# integrated_driver_and_current_sense.net
KiCad netlist of a schematic drawn in Altium Designer
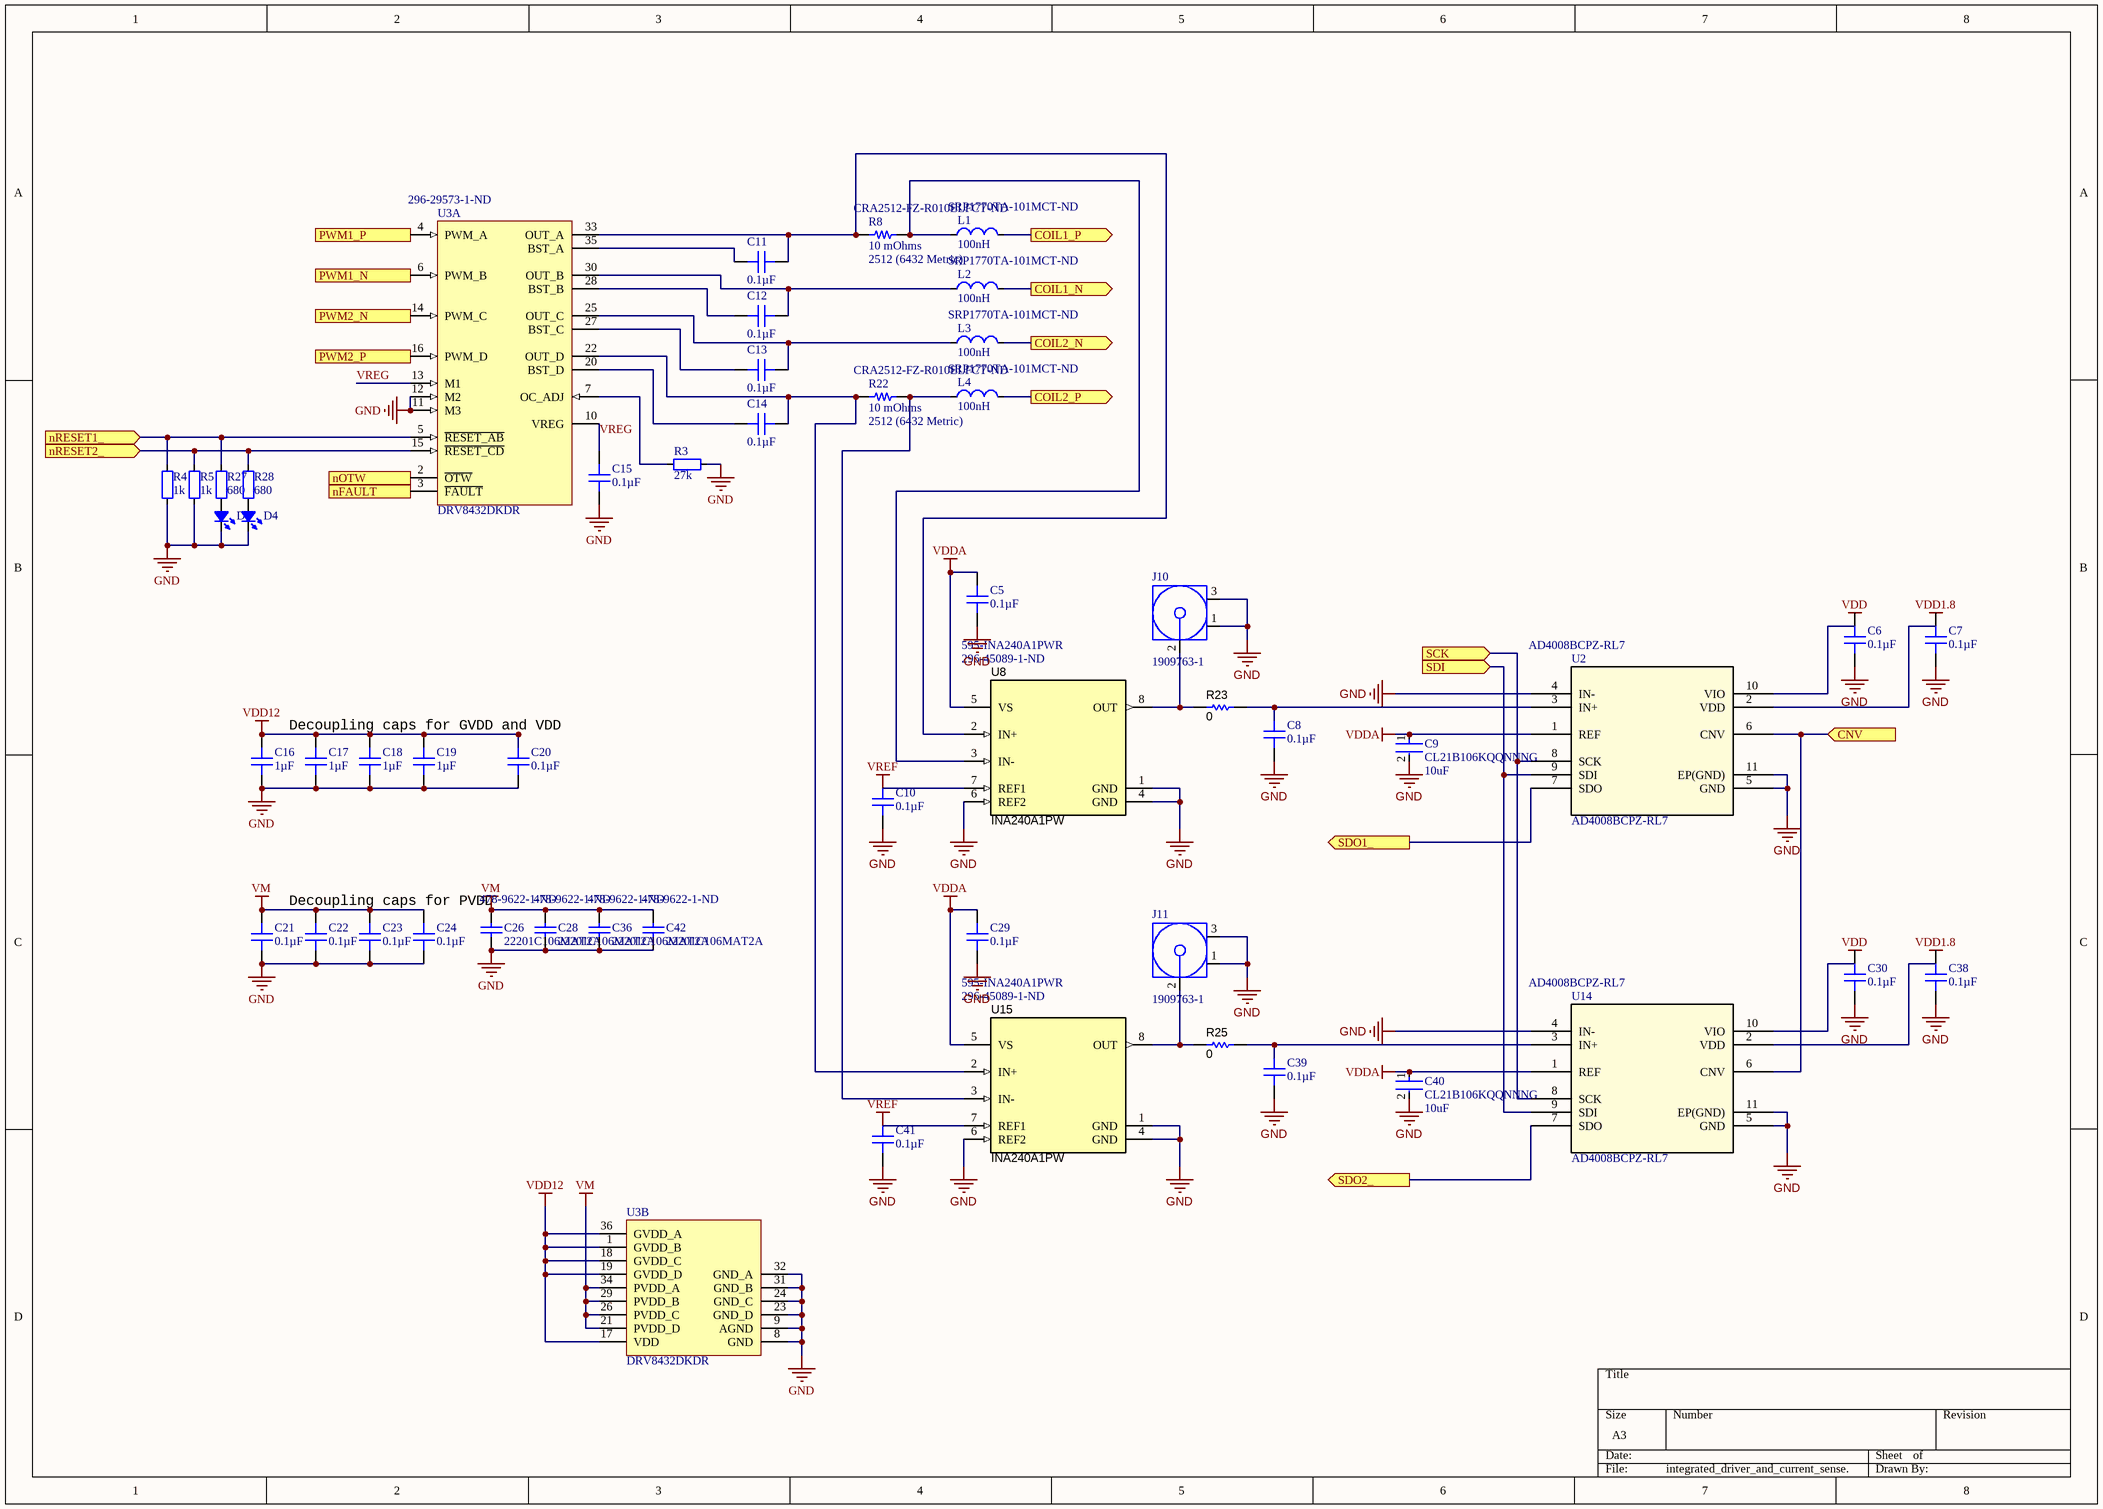
[diagram p0: integrated_driver_and_current_sense.SchDoc]

(export (version "E")
  (design (tool "Eeschema 10.0.6"))
  (components
    (comp (ref "C5")
      (value "0.1µF")
      (footprint "CAP 0402_1005")
      (description "CAP CER 0.1UF 25V X7R 0402")
      (fields (field (name "MANUFACTURER") "AVX Corporation") (field (name "PART NUMBER") "04023C104KAT2A"))
      (libsource (lib "Celestial Altium Library - altium_library") (part "Capacitor"))
    )
    (comp (ref "C6")
      (value "0.1µF")
      (footprint "CAP 0402_1005")
      (description "CAP CER 0.1UF 25V X7R 0402")
      (fields (field (name "MANUFACTURER") "AVX Corporation") (field (name "PART NUMBER") "04023C104KAT2A"))
      (libsource (lib "Celestial Altium Library - altium_library") (part "Capacitor"))
    )
    (comp (ref "C7")
      (value "0.1µF")
      (footprint "CAP 0402_1005")
      (description "CAP CER 0.1UF 25V X7R 0402")
      (fields (field (name "MANUFACTURER") "AVX Corporation") (field (name "PART NUMBER") "04023C104KAT2A"))
      (libsource (lib "Celestial Altium Library - altium_library") (part "Capacitor"))
    )
    (comp (ref "C8")
      (value "0.1µF")
      (footprint "CAP 0402_1005")
      (description "CAP CER 0.1UF 25V X7R 0402")
      (fields (field (name "MANUFACTURER") "AVX Corporation") (field (name "PART NUMBER") "04023C104KAT2A"))
      (libsource (lib "Celestial Altium Library - altium_library") (part "Capacitor"))
    )
    (comp (ref "C9")
      (value "CL21B106KQQNNNG")
      (footprint "FP-CL21-IPC_C")
      (description "CL21 Series 0805 10uF 6.3V ±10% Tolerance X7R Multilayer Ceramic Chip Capacitor")
      (fields
        (field (name "CAPACITANCE") "10uF")
        (field (name "TOLERANCE") "10%")
        (field (name "VOLTAGE") "6.3V")
      )
      (libsource (lib "Altium Content Vault") (part "b4654b650e69147ec39a6b967a45e02"))
    )
    (comp (ref "C10")
      (value "0.1µF")
      (footprint "CAP 0402_1005")
      (description "CAP CER 0.1UF 25V X7R 0402")
      (fields (field (name "MANUFACTURER") "AVX Corporation") (field (name "PART NUMBER") "04023C104KAT2A"))
      (libsource (lib "Celestial Altium Library - altium_library") (part "Capacitor"))
    )
    (comp (ref "C11")
      (value "0.1µF")
      (footprint "CAP 0603_1608")
      (description "CAP CER 0.1UF 100V X7R 0603")
      (fields (field (name "PART NUMBER") "06031C104KAT2A") (field (name "MANUFACTURER") "AVX Corporation"))
      (libsource (lib "Celestial Altium Library - altium_library") (part "Capacitor"))
    )
    (comp (ref "C12")
      (value "0.1µF")
      (footprint "CAP 0603_1608")
      (description "CAP CER 0.1UF 100V X7R 0603")
      (fields (field (name "PART NUMBER") "06031C104KAT2A") (field (name "MANUFACTURER") "AVX Corporation"))
      (libsource (lib "Celestial Altium Library - altium_library") (part "Capacitor"))
    )
    (comp (ref "C13")
      (value "0.1µF")
      (footprint "CAP 0603_1608")
      (description "CAP CER 0.1UF 100V X7R 0603")
      (fields (field (name "PART NUMBER") "06031C104KAT2A") (field (name "MANUFACTURER") "AVX Corporation"))
      (libsource (lib "Celestial Altium Library - altium_library") (part "Capacitor"))
    )
    (comp (ref "C14")
      (value "0.1µF")
      (footprint "CAP 0603_1608")
      (description "CAP CER 0.1UF 100V X7R 0603")
      (fields (field (name "PART NUMBER") "06031C104KAT2A") (field (name "MANUFACTURER") "AVX Corporation"))
      (libsource (lib "Celestial Altium Library - altium_library") (part "Capacitor"))
    )
    (comp (ref "C15")
      (value "0.1µF")
      (footprint "CAP 0402_1005")
      (description "CAP CER 0.1UF 25V X7R 0402")
      (fields (field (name "PART NUMBER") "04023C104KAT2A") (field (name "MANUFACTURER") "AVX Corporation"))
      (libsource (lib "Celestial Altium Library - altium_library") (part "Capacitor"))
    )
    (comp (ref "C16")
      (value "1µF")
      (footprint "CAP 0603_1608")
      (description "CAP CER 1UF 25V X7R 0603")
      (fields (field (name "PART NUMBER") "TMK107B7105KA-T") (field (name "MANUFACTURER") "Taiyo Yuden"))
      (libsource (lib "Celestial Altium Library - altium_library") (part "Capacitor"))
    )
    (comp (ref "C17")
      (value "1µF")
      (footprint "CAP 0603_1608")
      (description "CAP CER 1UF 25V X7R 0603")
      (fields (field (name "PART NUMBER") "TMK107B7105KA-T") (field (name "MANUFACTURER") "Taiyo Yuden"))
      (libsource (lib "Celestial Altium Library - altium_library") (part "Capacitor"))
    )
    (comp (ref "C18")
      (value "1µF")
      (footprint "CAP 0603_1608")
      (description "CAP CER 1UF 25V X7R 0603")
      (fields (field (name "PART NUMBER") "TMK107B7105KA-T") (field (name "MANUFACTURER") "Taiyo Yuden"))
      (libsource (lib "Celestial Altium Library - altium_library") (part "Capacitor"))
    )
    (comp (ref "C19")
      (value "1µF")
      (footprint "CAP 0603_1608")
      (description "CAP CER 1UF 25V X7R 0603")
      (fields (field (name "PART NUMBER") "TMK107B7105KA-T") (field (name "MANUFACTURER") "Taiyo Yuden"))
      (libsource (lib "Celestial Altium Library - altium_library") (part "Capacitor"))
    )
    (comp (ref "C20")
      (value "0.1µF")
      (footprint "CAP 0402_1005")
      (description "CAP CER 0.1UF 25V X7R 0402")
      (fields (field (name "MANUFACTURER") "AVX Corporation") (field (name "PART NUMBER") "04023C104KAT2A"))
      (libsource (lib "Celestial Altium Library - altium_library") (part "Capacitor"))
    )
    (comp (ref "C21")
      (value "0.1µF")
      (footprint "CAP 0603_1608")
      (description "CAP CER 0.1UF 100V X7R 0603")
      (fields (field (name "PART NUMBER") "06031C104KAT2A") (field (name "MANUFACTURER") "AVX Corporation"))
      (libsource (lib "Celestial Altium Library - altium_library") (part "Capacitor"))
    )
    (comp (ref "C22")
      (value "0.1µF")
      (footprint "CAP 0603_1608")
      (description "CAP CER 0.1UF 100V X7R 0603")
      (fields (field (name "PART NUMBER") "06031C104KAT2A") (field (name "MANUFACTURER") "AVX Corporation"))
      (libsource (lib "Celestial Altium Library - altium_library") (part "Capacitor"))
    )
    (comp (ref "C23")
      (value "0.1µF")
      (footprint "CAP 0603_1608")
      (description "CAP CER 0.1UF 100V X7R 0603")
      (fields (field (name "PART NUMBER") "06031C104KAT2A") (field (name "MANUFACTURER") "AVX Corporation"))
      (libsource (lib "Celestial Altium Library - altium_library") (part "Capacitor"))
    )
    (comp (ref "C24")
      (value "0.1µF")
      (footprint "CAP 0603_1608")
      (description "CAP CER 0.1UF 100V X7R 0603")
      (fields (field (name "PART NUMBER") "06031C104KAT2A") (field (name "MANUFACTURER") "AVX Corporation"))
      (libsource (lib "Celestial Altium Library - altium_library") (part "Capacitor"))
    )
    (comp (ref "C26")
      (value "22201C106MAT2A")
      (footprint "CAPC5750X279X64NL40T39")
      (description "Cap Ceramic 10uF 100V X7R 20% SMD 2220 125°C Embossed T/R")
      (fields (field (name "MANUFACTURER") "AVX") (field (name "SUPPLIER PART NUMBER 1") "478-9622-1-ND"))
      (libsource (lib "Altium Content Vault") (part "CAP-NP-2"))
    )
    (comp (ref "C28")
      (value "22201C106MAT2A")
      (footprint "CAPC5750X279X64NL40T39")
      (description "Cap Ceramic 10uF 100V X7R 20% SMD 2220 125°C Embossed T/R")
      (fields (field (name "MANUFACTURER") "AVX") (field (name "SUPPLIER PART NUMBER 1") "478-9622-1-ND"))
      (libsource (lib "Altium Content Vault") (part "CAP-NP-2"))
    )
    (comp (ref "C29")
      (value "0.1µF")
      (footprint "CAP 0402_1005")
      (description "CAP CER 0.1UF 25V X7R 0402")
      (fields (field (name "MANUFACTURER") "AVX Corporation") (field (name "PART NUMBER") "04023C104KAT2A"))
      (libsource (lib "Celestial Altium Library - altium_library") (part "Capacitor"))
    )
    (comp (ref "C30")
      (value "0.1µF")
      (footprint "CAP 0402_1005")
      (description "CAP CER 0.1UF 25V X7R 0402")
      (fields (field (name "MANUFACTURER") "AVX Corporation") (field (name "PART NUMBER") "04023C104KAT2A"))
      (libsource (lib "Celestial Altium Library - altium_library") (part "Capacitor"))
    )
    (comp (ref "C36")
      (value "22201C106MAT2A")
      (footprint "CAPC5750X279X64NL40T39")
      (description "Cap Ceramic 10uF 100V X7R 20% SMD 2220 125°C Embossed T/R")
      (fields (field (name "MANUFACTURER") "AVX") (field (name "SUPPLIER PART NUMBER 1") "478-9622-1-ND"))
      (libsource (lib "Altium Content Vault") (part "CAP-NP-2"))
    )
    (comp (ref "C38")
      (value "0.1µF")
      (footprint "CAP 0402_1005")
      (description "CAP CER 0.1UF 25V X7R 0402")
      (fields (field (name "MANUFACTURER") "AVX Corporation") (field (name "PART NUMBER") "04023C104KAT2A"))
      (libsource (lib "Celestial Altium Library - altium_library") (part "Capacitor"))
    )
    (comp (ref "C39")
      (value "0.1µF")
      (footprint "CAP 0402_1005")
      (description "CAP CER 0.1UF 25V X7R 0402")
      (fields (field (name "MANUFACTURER") "AVX Corporation") (field (name "PART NUMBER") "04023C104KAT2A"))
      (libsource (lib "Celestial Altium Library - altium_library") (part "Capacitor"))
    )
    (comp (ref "C40")
      (value "CL21B106KQQNNNG")
      (footprint "FP-CL21-IPC_C")
      (description "CL21 Series 0805 10uF 6.3V ±10% Tolerance X7R Multilayer Ceramic Chip Capacitor")
      (fields
        (field (name "CAPACITANCE") "10uF")
        (field (name "TOLERANCE") "10%")
        (field (name "VOLTAGE") "6.3V")
      )
      (libsource (lib "Altium Content Vault") (part "b4654b650e69147ec39a6b967a45e02"))
    )
    (comp (ref "C41")
      (value "0.1µF")
      (footprint "CAP 0402_1005")
      (description "CAP CER 0.1UF 25V X7R 0402")
      (fields (field (name "MANUFACTURER") "AVX Corporation") (field (name "PART NUMBER") "04023C104KAT2A"))
      (libsource (lib "Celestial Altium Library - altium_library") (part "Capacitor"))
    )
    (comp (ref "C42")
      (value "22201C106MAT2A")
      (footprint "CAPC5750X279X64NL40T39")
      (description "Cap Ceramic 10uF 100V X7R 20% SMD 2220 125°C Embossed T/R")
      (fields (field (name "MANUFACTURER") "AVX") (field (name "SUPPLIER PART NUMBER 1") "478-9622-1-ND"))
      (libsource (lib "Altium Content Vault") (part "CAP-NP-2"))
    )
    (comp (ref "D3")
      (value "LED_0402")
      (footprint "PCB_ActiveLED:LED_0402_RED")
      (description "LED")
      (libsource (lib "SCH_Active") (part "LED_0402"))
    )
    (comp (ref "D4")
      (value "LED_0402")
      (footprint "PCB_ActiveLED:LED_0402_RED")
      (description "LED")
      (libsource (lib "SCH_Active") (part "LED_0402"))
    )
    (comp (ref "J10")
      (value "1909763-1")
      (footprint "TECO-1909763-1_V")
      (description "Ultra Miniature Coaxial Connector Jack, 60 V, 50 Ohm, -40 to 90 degC, RoHS, Tape and Reel")
      (fields (field (name "MANUFACTURER") "TE Connectivity"))
      (libsource (lib "Altium Content Vault") (part "CN-1P-M-RF3"))
    )
    (comp (ref "J11")
      (value "1909763-1")
      (footprint "TECO-1909763-1_V")
      (description "Ultra Miniature Coaxial Connector Jack, 60 V, 50 Ohm, -40 to 90 degC, RoHS, Tape and Reel")
      (fields (field (name "MANUFACTURER") "TE Connectivity"))
      (libsource (lib "Altium Content Vault") (part "CN-1P-M-RF3"))
    )
    (comp (ref "L1")
      (value "100nH")
      (footprint "SRP1770TA")
      (description "FIXED IND 100UH 5.3A 118 MOHM")
      (fields
        (field (name "MANUFACTURER") "TDK")
        (field (name "MANUFACTURER PART NUMBER") "MPZ2012S300AT000")
        (field (name "SUPPLIER PART NUMBER 1") "SRP1770TA-101MCT-ND")
      )
      (libsource (lib "SCH_Passive") (part "Ind_0805"))
    )
    (comp (ref "L2")
      (value "100nH")
      (footprint "SRP1770TA")
      (description "FIXED IND 100UH 5.3A 118 MOHM")
      (fields
        (field (name "MANUFACTURER") "TDK")
        (field (name "MANUFACTURER PART NUMBER") "MPZ2012S300AT000")
        (field (name "SUPPLIER PART NUMBER 1") "SRP1770TA-101MCT-ND")
      )
      (libsource (lib "SCH_Passive") (part "Ind_0805"))
    )
    (comp (ref "L3")
      (value "100nH")
      (footprint "SRP1770TA")
      (description "FIXED IND 100UH 5.3A 118 MOHM")
      (fields
        (field (name "MANUFACTURER") "TDK")
        (field (name "MANUFACTURER PART NUMBER") "MPZ2012S300AT000")
        (field (name "SUPPLIER PART NUMBER 1") "SRP1770TA-101MCT-ND")
      )
      (libsource (lib "SCH_Passive") (part "Ind_0805"))
    )
    (comp (ref "L4")
      (value "100nH")
      (footprint "SRP1770TA")
      (description "FIXED IND 100UH 5.3A 118 MOHM")
      (fields
        (field (name "MANUFACTURER") "TDK")
        (field (name "MANUFACTURER PART NUMBER") "MPZ2012S300AT000")
        (field (name "SUPPLIER PART NUMBER 1") "SRP1770TA-101MCT-ND")
      )
      (libsource (lib "SCH_Passive") (part "Ind_0805"))
    )
    (comp (ref "R3")
      (value "27k")
      (footprint "PCB_PassiveRes:RES_0402")
      (description "Resistor")
      (fields (field (name "Comment") "Res_0402"))
      (libsource (lib "") (part "Res_0402_1"))
    )
    (comp (ref "R4")
      (value "1k")
      (footprint "PCB_PassiveRes:RES_0805")
      (description "Resistor")
      (fields (field (name "Comment") "Res_0805"))
      (libsource (lib "SCH_Passive") (part "Res_0805"))
    )
    (comp (ref "R5")
      (value "1k")
      (footprint "PCB_PassiveRes:RES_0805")
      (description "Resistor")
      (fields (field (name "Comment") "Res_0805"))
      (libsource (lib "SCH_Passive") (part "Res_0805"))
    )
    (comp (ref "R8")
      (value "10 mOhms")
      (footprint "STACKPOLE CSR2512")
      (description "RES 0.01 OHM 1% 2W 2512")
      (fields
        (field (name "PART NUMBER") "TLR3A20ER010FTDG")
        (field (name "PACKAGE / CASE") "2512 (6432 Metric)")
        (field (name "MANUFACTURER") "TE Connectivity Passive Product")
        (field (name "SUPPLIER PART NUMBER 1") "CRA2512-FZ-R010ELFCT-ND")
      )
      (libsource (lib "Celestial Altium Library - altium_library") (part "Resistor"))
    )
    (comp (ref "R22")
      (value "10 mOhms")
      (footprint "STACKPOLE CSR2512")
      (description "RES 0.01 OHM 1% 2W 2512")
      (fields
        (field (name "PART NUMBER") "TLR3A20ER010FTDG")
        (field (name "PACKAGE / CASE") "2512 (6432 Metric)")
        (field (name "MANUFACTURER") "TE Connectivity Passive Product")
        (field (name "SUPPLIER PART NUMBER 1") "CRA2512-FZ-R010ELFCT-ND")
      )
      (libsource (lib "Celestial Altium Library - altium_library") (part "Resistor"))
    )
    (comp (ref "R23")
      (value "CRCW04020000Z0ED")
      (footprint "RES_0402")
      (description "RES, 0, 5%, 0.063 W, 0402")
      (fields
        (field (name "VALUEDISPLAYED") "0")
        (field (name "MANUFACTURER") "Vishay-Dale")
        (field (name "PUBLISHER") "Texas Instruments")
      )
      (libsource (lib "Resistor_0402") (part "CRCW04020000Z0ED"))
    )
    (comp (ref "R25")
      (value "CRCW04020000Z0ED")
      (footprint "RES_0402")
      (description "RES, 0, 5%, 0.063 W, 0402")
      (fields
        (field (name "VALUEDISPLAYED") "0")
        (field (name "MANUFACTURER") "Vishay-Dale")
        (field (name "PUBLISHER") "Texas Instruments")
      )
      (libsource (lib "Resistor_0402") (part "CRCW04020000Z0ED"))
    )
    (comp (ref "R27")
      (value "680")
      (footprint "PCB_PassiveRes:RES_0402")
      (description "Resistor")
      (fields (field (name "Comment") "Res_0402"))
      (libsource (lib "SCH_Passive") (part "Res_0402"))
    )
    (comp (ref "R28")
      (value "680")
      (footprint "PCB_PassiveRes:RES_0402")
      (description "Resistor")
      (fields (field (name "Comment") "Res_0402"))
      (libsource (lib "SCH_Passive") (part "Res_0402"))
    )
    (comp (ref "U2")
      (value "AD4008BCPZ-RL7")
      (footprint "CP_10_9")
      (description "16-Bit, 2 MSPS/1 MSPS/500 kSPS,\r\nPrecision, Pseudo Differential, SAR ADCs")
      (fields (field (name "SUPPLIER PART NUMBER 1") "AD4008BCPZ-RL7"))
      (libsource (lib "2018-05-09_17-49-12") (part "AD4008BCPZ-RL7"))
    )
    (comp (ref "U3")
      (value "DRV8432DKDR")
      (footprint "DKD0036A_N")
      (description "TEXAS INSTRUMENTS - DRV8432DKDR - MOTOR CONTROLLER, FULL BRIDGE, HSSOP-36")
      (fields
        (field (name "SUPPLIER PART NUMBER 1") "296-29573-1-ND")
        (field (name "MANUFACTURER") "Texas Instruments")
      )
      (libsource (lib "Altium Content Vault") (part "TI-DRV8432DKD36"))
    )
    (comp (ref "U8")
      (value "INA240A1PW")
      (footprint "PW0008A_N")
      (description "TEXAS INSTRUMENTS - INA240A1PWR . - CURRENT SENSE AMPLIFIER, 400KHZ, TSSOP-8")
      (fields
        (field (name "MANUFACTURER") "Texas Instruments")
        (field (name "MANUFACTURER PART NUMBER") "INA240A1PWR")
        (field (name "SUPPLIER PART NUMBER 1") "296-45089-1-ND")
        (field (name "SUPPLIER PART NUMBER 2") "595-INA240A1PWR")
        (field (name "SYMBOLCREATOR") "Altium")
        (field (name "PUBLISHER") "Texas Instruments")
      )
      (libsource (lib "TI_Pre_RTM") (part "INA240A1PW"))
    )
    (comp (ref "U14")
      (value "AD4008BCPZ-RL7")
      (footprint "CP_10_9")
      (description "16-Bit, 2 MSPS/1 MSPS/500 kSPS,\r\nPrecision, Pseudo Differential, SAR ADCs")
      (fields (field (name "SUPPLIER PART NUMBER 1") "AD4008BCPZ-RL7"))
      (libsource (lib "2018-05-09_17-49-12") (part "AD4008BCPZ-RL7"))
    )
    (comp (ref "U15")
      (value "INA240A1PW")
      (footprint "PW0008A_N")
      (description "TEXAS INSTRUMENTS - INA240A1PWR . - CURRENT SENSE AMPLIFIER, 400KHZ, TSSOP-8")
      (fields
        (field (name "MANUFACTURER") "Texas Instruments")
        (field (name "MANUFACTURER PART NUMBER") "INA240A1PWR")
        (field (name "SUPPLIER PART NUMBER 1") "296-45089-1-ND")
        (field (name "SUPPLIER PART NUMBER 2") "595-INA240A1PWR")
        (field (name "SYMBOLCREATOR") "Altium")
        (field (name "PUBLISHER") "Texas Instruments")
      )
      (libsource (lib "TI_Pre_RTM") (part "INA240A1PW"))
    )
  )
  (nets
    (net (code "1") (name "/CNV") (class "Default")
      (node (ref "U14") (pin "6") (pinfunction "CNV_6") (pintype "passive"))
      (node (ref "U2") (pin "6") (pinfunction "CNV_6") (pintype "passive"))
    )
    (net (code "2") (name "/COIL1_N") (class "Default")
      (node (ref "L2") (pin "2") (pinfunction "2_2") (pintype "passive"))
    )
    (net (code "3") (name "/COIL1_P") (class "Default")
      (node (ref "L1") (pin "2") (pinfunction "2_2") (pintype "passive"))
    )
    (net (code "4") (name "/COIL2_N") (class "Default")
      (node (ref "L3") (pin "2") (pinfunction "2_2") (pintype "passive"))
    )
    (net (code "5") (name "/COIL2_P") (class "Default")
      (node (ref "L4") (pin "2") (pinfunction "2_2") (pintype "passive"))
    )
    (net (code "6") (name "/PWM1_N") (class "Default")
      (node (ref "U3") (pin "6") (pinfunction "PWM_B_6") (pintype "input"))
    )
    (net (code "7") (name "/PWM1_P") (class "Default")
      (node (ref "U3") (pin "4") (pinfunction "PWM_A_4") (pintype "input"))
    )
    (net (code "8") (name "/PWM2_N") (class "Default")
      (node (ref "U3") (pin "14") (pinfunction "PWM_C_14") (pintype "input"))
    )
    (net (code "9") (name "/PWM2_P") (class "Default")
      (node (ref "U3") (pin "16") (pinfunction "PWM_D_16") (pintype "input"))
    )
    (net (code "10") (name "/SCK") (class "Default")
      (node (ref "U14") (pin "8") (pinfunction "SCK_8") (pintype "passive"))
      (node (ref "U2") (pin "8") (pinfunction "SCK_8") (pintype "passive"))
    )
    (net (code "11") (name "/SDI") (class "Default")
      (node (ref "U14") (pin "9") (pinfunction "SDI_9") (pintype "passive"))
      (node (ref "U2") (pin "9") (pinfunction "SDI_9") (pintype "passive"))
    )
    (net (code "12") (name "/SDO1_") (class "Default")
      (node (ref "U2") (pin "7") (pinfunction "SDO_7") (pintype "passive"))
    )
    (net (code "13") (name "/SDO2_") (class "Default")
      (node (ref "U14") (pin "7") (pinfunction "SDO_7") (pintype "passive"))
    )
    (net (code "14") (name "/VREG") (class "Default")
      (node (ref "C15") (pin "1") (pinfunction "1_1") (pintype "passive"))
      (node (ref "U3") (pin "10") (pinfunction "VREG_10") (pintype "passive"))
      (node (ref "U3") (pin "13") (pinfunction "M1_13") (pintype "input"))
    )
    (net (code "15") (name "/nFAULT") (class "Default")
      (node (ref "U3") (pin "3") (pinfunction "~{FAULT}_3") (pintype "open_collector"))
    )
    (net (code "16") (name "/nOTW") (class "Default")
      (node (ref "U3") (pin "2") (pinfunction "~{OTW}_2") (pintype "open_collector"))
    )
    (net (code "17") (name "/nRESET1_") (class "Default")
      (node (ref "R27") (pin "2") (pinfunction "2_2") (pintype "passive"))
      (node (ref "R4") (pin "2") (pinfunction "2_2") (pintype "passive"))
      (node (ref "U3") (pin "5") (pinfunction "~{RESET_AB}_5") (pintype "input"))
    )
    (net (code "18") (name "/nRESET2_") (class "Default")
      (node (ref "R28") (pin "2") (pinfunction "2_2") (pintype "passive"))
      (node (ref "R5") (pin "2") (pinfunction "2_2") (pintype "passive"))
      (node (ref "U3") (pin "15") (pinfunction "~{RESET_CD}_15") (pintype "input"))
    )
    (net (code "19") (name "GND") (class "Default")
      (node (ref "C10") (pin "2") (pinfunction "2_2") (pintype "passive"))
      (node (ref "C15") (pin "2") (pinfunction "2_2") (pintype "passive"))
      (node (ref "C16") (pin "2") (pinfunction "2_2") (pintype "passive"))
      (node (ref "C17") (pin "2") (pinfunction "2_2") (pintype "passive"))
      (node (ref "C18") (pin "2") (pinfunction "2_2") (pintype "passive"))
      (node (ref "C19") (pin "2") (pinfunction "2_2") (pintype "passive"))
      (node (ref "C20") (pin "2") (pinfunction "2_2") (pintype "passive"))
      (node (ref "C21") (pin "2") (pinfunction "2_2") (pintype "passive"))
      (node (ref "C22") (pin "2") (pinfunction "2_2") (pintype "passive"))
      (node (ref "C23") (pin "2") (pinfunction "2_2") (pintype "passive"))
      (node (ref "C24") (pin "2") (pinfunction "2_2") (pintype "passive"))
      (node (ref "C26") (pin "2") (pinfunction "2_2") (pintype "passive"))
      (node (ref "C28") (pin "2") (pinfunction "2_2") (pintype "passive"))
      (node (ref "C29") (pin "2") (pinfunction "2_2") (pintype "passive"))
      (node (ref "C30") (pin "2") (pinfunction "2_2") (pintype "passive"))
      (node (ref "C36") (pin "2") (pinfunction "2_2") (pintype "passive"))
      (node (ref "C38") (pin "2") (pinfunction "2_2") (pintype "passive"))
      (node (ref "C39") (pin "2") (pinfunction "2_2") (pintype "passive"))
      (node (ref "C40") (pin "2") (pinfunction "2_2") (pintype "passive"))
      (node (ref "C41") (pin "2") (pinfunction "2_2") (pintype "passive"))
      (node (ref "C42") (pin "2") (pinfunction "2_2") (pintype "passive"))
      (node (ref "C5") (pin "2") (pinfunction "2_2") (pintype "passive"))
      (node (ref "C6") (pin "2") (pinfunction "2_2") (pintype "passive"))
      (node (ref "C7") (pin "2") (pinfunction "2_2") (pintype "passive"))
      (node (ref "C8") (pin "2") (pinfunction "2_2") (pintype "passive"))
      (node (ref "C9") (pin "2") (pinfunction "2_2") (pintype "passive"))
      (node (ref "D3") (pin "2") (pinfunction "K_2") (pintype "passive"))
      (node (ref "D4") (pin "2") (pinfunction "K_2") (pintype "passive"))
      (node (ref "J10") (pin "1") (pinfunction "1_1") (pintype "passive"))
      (node (ref "J10") (pin "3") (pinfunction "3_3") (pintype "passive"))
      (node (ref "J11") (pin "1") (pinfunction "1_1") (pintype "passive"))
      (node (ref "J11") (pin "3") (pinfunction "3_3") (pintype "passive"))
      (node (ref "R3") (pin "2") (pinfunction "2_2") (pintype "passive"))
      (node (ref "R4") (pin "1") (pinfunction "1_1") (pintype "passive"))
      (node (ref "R5") (pin "1") (pinfunction "1_1") (pintype "passive"))
      (node (ref "U14") (pin "11") (pinfunction "EP(GND)_11") (pintype "passive"))
      (node (ref "U14") (pin "4") (pinfunction "IN-_4") (pintype "passive"))
      (node (ref "U14") (pin "5") (pinfunction "GND_5") (pintype "passive"))
      (node (ref "U15") (pin "1") (pinfunction "GND_1") (pintype "power_in"))
      (node (ref "U15") (pin "4") (pinfunction "GND_4") (pintype "power_in"))
      (node (ref "U15") (pin "6") (pinfunction "REF2_6") (pintype "input"))
      (node (ref "U2") (pin "11") (pinfunction "EP(GND)_11") (pintype "passive"))
      (node (ref "U2") (pin "4") (pinfunction "IN-_4") (pintype "passive"))
      (node (ref "U2") (pin "5") (pinfunction "GND_5") (pintype "passive"))
      (node (ref "U3") (pin "11") (pinfunction "M3_11") (pintype "input"))
      (node (ref "U3") (pin "12") (pinfunction "M2_12") (pintype "input"))
      (node (ref "U3") (pin "23") (pinfunction "GND_D_23") (pintype "power_in"))
      (node (ref "U3") (pin "24") (pinfunction "GND_C_24") (pintype "power_in"))
      (node (ref "U3") (pin "31") (pinfunction "GND_B_31") (pintype "power_in"))
      (node (ref "U3") (pin "32") (pinfunction "GND_A_32") (pintype "power_in"))
      (node (ref "U3") (pin "8") (pinfunction "GND_8") (pintype "power_in"))
      (node (ref "U3") (pin "9") (pinfunction "AGND_9") (pintype "power_in"))
      (node (ref "U8") (pin "1") (pinfunction "GND_1") (pintype "power_in"))
      (node (ref "U8") (pin "4") (pinfunction "GND_4") (pintype "power_in"))
      (node (ref "U8") (pin "6") (pinfunction "REF2_6") (pintype "input"))
    )
    (net (code "20") (name "Net-(D3-A)") (class "Default")
      (node (ref "D3") (pin "1") (pinfunction "A_1") (pintype "passive"))
      (node (ref "R27") (pin "1") (pinfunction "1_1") (pintype "passive"))
    )
    (net (code "21") (name "Net-(D4-A)") (class "Default")
      (node (ref "D4") (pin "1") (pinfunction "A_1") (pintype "passive"))
      (node (ref "R28") (pin "1") (pinfunction "1_1") (pintype "passive"))
    )
    (net (code "22") (name "Net-(U2-IN+)") (class "Default")
      (node (ref "C8") (pin "1") (pinfunction "1_1") (pintype "passive"))
      (node (ref "R23") (pin "1") (pinfunction "1_1") (pintype "passive"))
      (node (ref "U2") (pin "3") (pinfunction "IN+_3") (pintype "passive"))
    )
    (net (code "23") (name "Net-(U3A-BST_A)") (class "Default")
      (node (ref "C11") (pin "1") (pinfunction "1_1") (pintype "passive"))
      (node (ref "U3") (pin "35") (pinfunction "BST_A_35") (pintype "passive"))
    )
    (net (code "24") (name "Net-(U3A-BST_B)") (class "Default")
      (node (ref "C12") (pin "1") (pinfunction "1_1") (pintype "passive"))
      (node (ref "U3") (pin "28") (pinfunction "BST_B_28") (pintype "passive"))
    )
    (net (code "25") (name "Net-(U3A-BST_C)") (class "Default")
      (node (ref "C13") (pin "1") (pinfunction "1_1") (pintype "passive"))
      (node (ref "U3") (pin "27") (pinfunction "BST_C_27") (pintype "passive"))
    )
    (net (code "26") (name "Net-(U3A-BST_D)") (class "Default")
      (node (ref "C14") (pin "1") (pinfunction "1_1") (pintype "passive"))
      (node (ref "U3") (pin "20") (pinfunction "BST_D_20") (pintype "passive"))
    )
    (net (code "27") (name "Net-(U3A-OC_ADJ)") (class "Default")
      (node (ref "R3") (pin "1") (pinfunction "1_1") (pintype "passive"))
      (node (ref "U3") (pin "7") (pinfunction "OC_ADJ_7") (pintype "input"))
    )
    (net (code "28") (name "Net-(U3A-OUT_A)") (class "Default")
      (node (ref "C11") (pin "2") (pinfunction "2_2") (pintype "passive"))
      (node (ref "R8") (pin "1") (pinfunction "1_1") (pintype "passive"))
      (node (ref "U3") (pin "33") (pinfunction "OUT_A_33") (pintype "tri_state"))
      (node (ref "U8") (pin "2") (pinfunction "IN+_2") (pintype "input"))
    )
    (net (code "29") (name "Net-(U3A-OUT_B)") (class "Default")
      (node (ref "C12") (pin "2") (pinfunction "2_2") (pintype "passive"))
      (node (ref "L2") (pin "1") (pinfunction "1_1") (pintype "passive"))
      (node (ref "U3") (pin "30") (pinfunction "OUT_B_30") (pintype "tri_state"))
    )
    (net (code "30") (name "Net-(U3A-OUT_C)") (class "Default")
      (node (ref "C13") (pin "2") (pinfunction "2_2") (pintype "passive"))
      (node (ref "L3") (pin "1") (pinfunction "1_1") (pintype "passive"))
      (node (ref "U3") (pin "25") (pinfunction "OUT_C_25") (pintype "tri_state"))
    )
    (net (code "31") (name "Net-(U8-IN-)") (class "Default")
      (node (ref "L1") (pin "1") (pinfunction "1_1") (pintype "passive"))
      (node (ref "R8") (pin "2") (pinfunction "2_2") (pintype "passive"))
      (node (ref "U8") (pin "3") (pinfunction "IN-_3") (pintype "input"))
    )
    (net (code "32") (name "Net-(U8-OUT)") (class "Default")
      (node (ref "J10") (pin "2") (pinfunction "2_2") (pintype "passive"))
      (node (ref "R23") (pin "2") (pinfunction "2_2") (pintype "passive"))
      (node (ref "U8") (pin "8") (pinfunction "OUT_8") (pintype "output"))
    )
    (net (code "33") (name "Net-(U14-IN+)") (class "Default")
      (node (ref "C39") (pin "1") (pinfunction "1_1") (pintype "passive"))
      (node (ref "R25") (pin "1") (pinfunction "1_1") (pintype "passive"))
      (node (ref "U14") (pin "3") (pinfunction "IN+_3") (pintype "passive"))
    )
    (net (code "34") (name "Net-(U15-IN+)") (class "Default")
      (node (ref "C14") (pin "2") (pinfunction "2_2") (pintype "passive"))
      (node (ref "R22") (pin "1") (pinfunction "1_1") (pintype "passive"))
      (node (ref "U15") (pin "2") (pinfunction "IN+_2") (pintype "input"))
      (node (ref "U3") (pin "22") (pinfunction "OUT_D_22") (pintype "tri_state"))
    )
    (net (code "35") (name "Net-(U15-IN-)") (class "Default")
      (node (ref "L4") (pin "1") (pinfunction "1_1") (pintype "passive"))
      (node (ref "R22") (pin "2") (pinfunction "2_2") (pintype "passive"))
      (node (ref "U15") (pin "3") (pinfunction "IN-_3") (pintype "input"))
    )
    (net (code "36") (name "Net-(U15-OUT)") (class "Default")
      (node (ref "J11") (pin "2") (pinfunction "2_2") (pintype "passive"))
      (node (ref "R25") (pin "2") (pinfunction "2_2") (pintype "passive"))
      (node (ref "U15") (pin "8") (pinfunction "OUT_8") (pintype "output"))
    )
    (net (code "37") (name "VDD") (class "Default")
      (node (ref "U14") (pin "10") (pinfunction "VIO_10") (pintype "passive"))
      (node (ref "U2") (pin "10") (pinfunction "VIO_10") (pintype "passive"))
    )
    (net (code "38") (name "VDD1.8") (class "Default")
      (node (ref "U14") (pin "2") (pinfunction "VDD_2") (pintype "passive"))
      (node (ref "U2") (pin "2") (pinfunction "VDD_2") (pintype "passive"))
    )
    (net (code "39") (name "VDD12") (class "Default")
      (node (ref "C16") (pin "1") (pinfunction "1_1") (pintype "passive"))
      (node (ref "C17") (pin "1") (pinfunction "1_1") (pintype "passive"))
      (node (ref "C18") (pin "1") (pinfunction "1_1") (pintype "passive"))
      (node (ref "C19") (pin "1") (pinfunction "1_1") (pintype "passive"))
      (node (ref "C20") (pin "1") (pinfunction "1_1") (pintype "passive"))
      (node (ref "U3") (pin "1") (pinfunction "GVDD_B_1") (pintype "power_in"))
      (node (ref "U3") (pin "17") (pinfunction "VDD_17") (pintype "power_in"))
      (node (ref "U3") (pin "18") (pinfunction "GVDD_C_18") (pintype "power_in"))
      (node (ref "U3") (pin "19") (pinfunction "GVDD_D_19") (pintype "power_in"))
      (node (ref "U3") (pin "36") (pinfunction "GVDD_A_36") (pintype "power_in"))
    )
    (net (code "40") (name "VDDA") (class "Default")
      (node (ref "C29") (pin "1") (pinfunction "1_1") (pintype "passive"))
      (node (ref "C40") (pin "1") (pinfunction "1_1") (pintype "passive"))
      (node (ref "C5") (pin "1") (pinfunction "1_1") (pintype "passive"))
      (node (ref "C9") (pin "1") (pinfunction "1_1") (pintype "passive"))
      (node (ref "U14") (pin "1") (pinfunction "REF_1") (pintype "passive"))
      (node (ref "U15") (pin "5") (pinfunction "VS_5") (pintype "power_in"))
      (node (ref "U2") (pin "1") (pinfunction "REF_1") (pintype "passive"))
      (node (ref "U8") (pin "5") (pinfunction "VS_5") (pintype "power_in"))
    )
    (net (code "41") (name "VM") (class "Default")
      (node (ref "C21") (pin "1") (pinfunction "1_1") (pintype "passive"))
      (node (ref "C22") (pin "1") (pinfunction "1_1") (pintype "passive"))
      (node (ref "C23") (pin "1") (pinfunction "1_1") (pintype "passive"))
      (node (ref "C24") (pin "1") (pinfunction "1_1") (pintype "passive"))
      (node (ref "C26") (pin "1") (pinfunction "1_1") (pintype "passive"))
      (node (ref "C28") (pin "1") (pinfunction "1_1") (pintype "passive"))
      (node (ref "C36") (pin "1") (pinfunction "1_1") (pintype "passive"))
      (node (ref "C42") (pin "1") (pinfunction "1_1") (pintype "passive"))
      (node (ref "U3") (pin "21") (pinfunction "PVDD_D_21") (pintype "power_in"))
      (node (ref "U3") (pin "26") (pinfunction "PVDD_C_26") (pintype "power_in"))
      (node (ref "U3") (pin "29") (pinfunction "PVDD_B_29") (pintype "power_in"))
      (node (ref "U3") (pin "34") (pinfunction "PVDD_A_34") (pintype "power_in"))
    )
    (net (code "42") (name "VREF") (class "Default")
      (node (ref "U15") (pin "7") (pinfunction "REF1_7") (pintype "input"))
      (node (ref "U8") (pin "7") (pinfunction "REF1_7") (pintype "input"))
    )
    (net (code "43") (name "unconnected-(C6-Pad1)") (class "Default")
      (node (ref "C6") (pin "1") (pinfunction "1_1") (pintype "passive"))
    )
    (net (code "44") (name "unconnected-(C7-Pad1)") (class "Default")
      (node (ref "C7") (pin "1") (pinfunction "1_1") (pintype "passive"))
    )
    (net (code "45") (name "unconnected-(C10-Pad1)") (class "Default")
      (node (ref "C10") (pin "1") (pinfunction "1_1") (pintype "passive"))
    )
    (net (code "46") (name "unconnected-(C30-Pad1)") (class "Default")
      (node (ref "C30") (pin "1") (pinfunction "1_1") (pintype "passive"))
    )
    (net (code "47") (name "unconnected-(C38-Pad1)") (class "Default")
      (node (ref "C38") (pin "1") (pinfunction "1_1") (pintype "passive"))
    )
    (net (code "48") (name "unconnected-(C41-Pad1)") (class "Default")
      (node (ref "C41") (pin "1") (pinfunction "1_1") (pintype "passive"))
    )
  )
)
